# DSO_Counters.net
KiCad netlist of a schematic drawn in Altium Designer
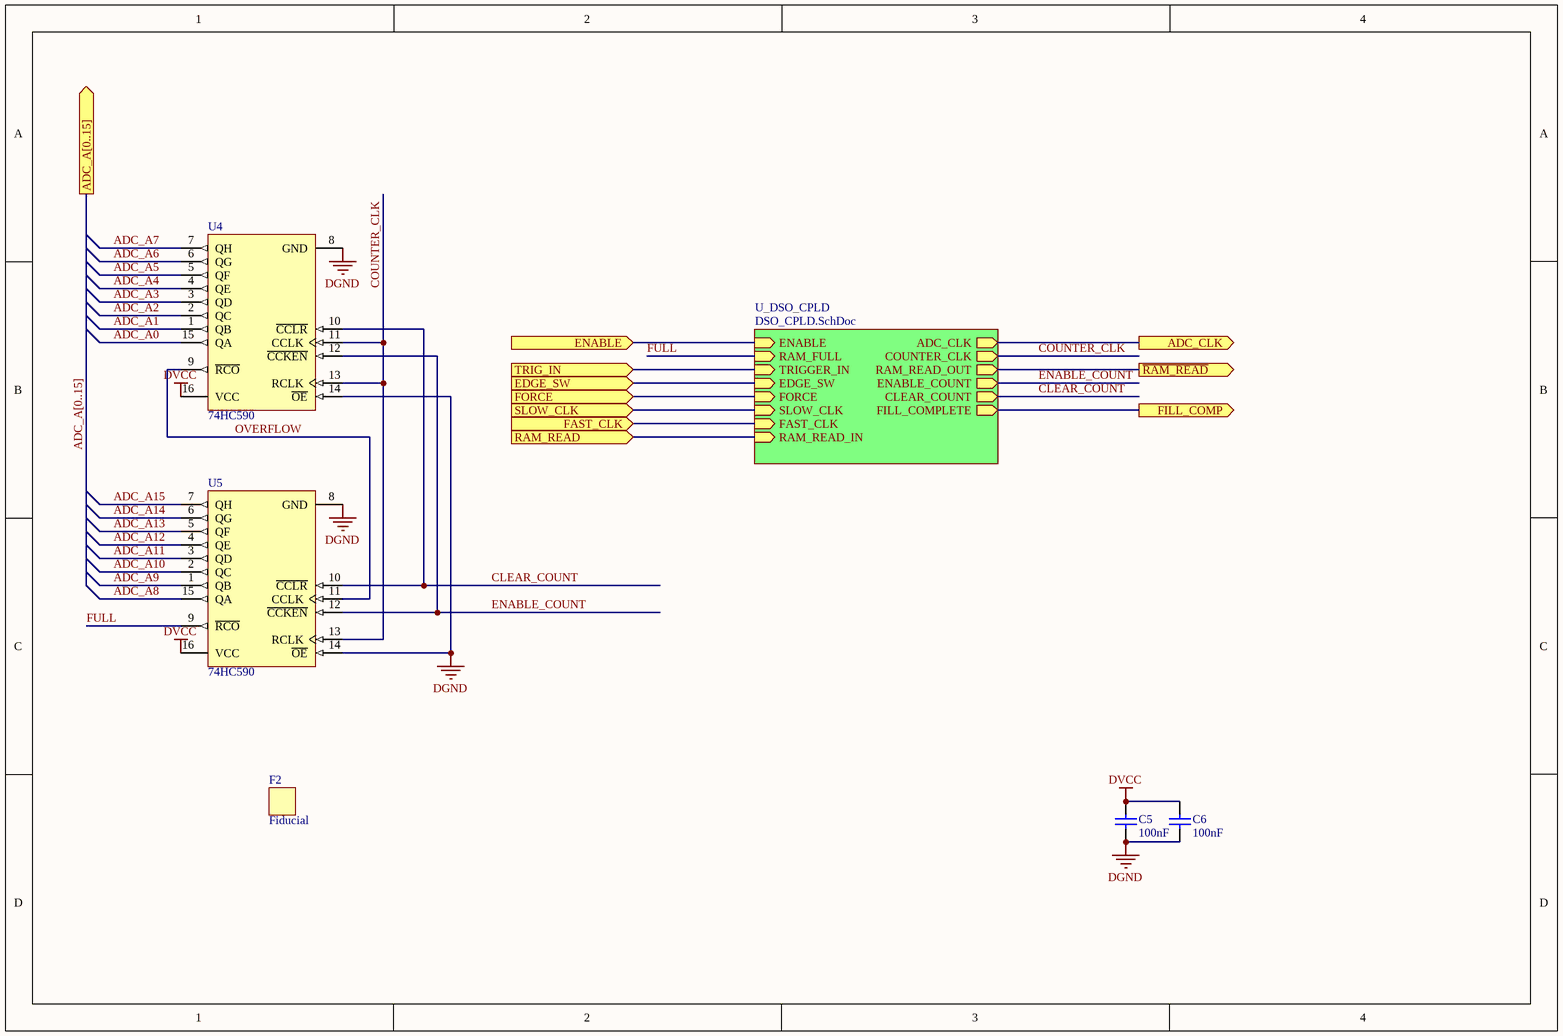
[diagram p0: DSO_Counters.SchDoc]

(export (version "E")
  (design (tool "Eeschema 10.0.6"))
  (components
    (comp (ref "C5")
      (value "100nF")
      (footprint "0805C")
      (description "Capacitor")
      (fields (field (name "REVIEWED BY") "RM - 2018/08/05"))
      (libsource (lib "DSO") (part "C"))
    )
    (comp (ref "C6")
      (value "100nF")
      (footprint "0805C")
      (description "Capacitor")
      (fields (field (name "REVIEWED BY") "RM - 2018/08/05"))
      (libsource (lib "DSO") (part "C"))
    )
    (comp (ref "F2") (value "Fiducial") (footprint "Fiducial") (libsource (lib "DSO") (part "Fiducial")))
    (comp (ref "U4")
      (value "74HC590")
      (footprint "SOIC-16")
      (description "8-Bit Binary Counter Register")
      (fields (field (name "REVIEWED BY") "RM - 2018/08/05"))
      (libsource (lib "DSO") (part "74HC590"))
    )
    (comp (ref "U5")
      (value "74HC590")
      (footprint "SOIC-16")
      (description "8-Bit Binary Counter Register")
      (fields (field (name "REVIEWED BY") "RM - 2018/08/05"))
      (libsource (lib "DSO") (part "74HC590"))
    )
  )
  (nets
    (net (code "1") (name "/ADC_A0") (class "Default")
      (node (ref "U4") (pin "15") (pinfunction "QA_15") (pintype "output"))
    )
    (net (code "2") (name "/ADC_A1") (class "Default")
      (node (ref "U4") (pin "1") (pinfunction "QB_1") (pintype "output"))
    )
    (net (code "3") (name "/ADC_A2") (class "Default")
      (node (ref "U4") (pin "2") (pinfunction "QC_2") (pintype "output"))
    )
    (net (code "4") (name "/ADC_A3") (class "Default")
      (node (ref "U4") (pin "3") (pinfunction "QD_3") (pintype "output"))
    )
    (net (code "5") (name "/ADC_A4") (class "Default")
      (node (ref "U4") (pin "4") (pinfunction "QE_4") (pintype "output"))
    )
    (net (code "6") (name "/ADC_A5") (class "Default")
      (node (ref "U4") (pin "5") (pinfunction "QF_5") (pintype "output"))
    )
    (net (code "7") (name "/ADC_A6") (class "Default")
      (node (ref "U4") (pin "6") (pinfunction "QG_6") (pintype "output"))
    )
    (net (code "8") (name "/ADC_A7") (class "Default")
      (node (ref "U4") (pin "7") (pinfunction "QH_7") (pintype "output"))
    )
    (net (code "9") (name "/ADC_A8") (class "Default")
      (node (ref "U5") (pin "15") (pinfunction "QA_15") (pintype "output"))
    )
    (net (code "10") (name "/ADC_A9") (class "Default")
      (node (ref "U5") (pin "1") (pinfunction "QB_1") (pintype "output"))
    )
    (net (code "11") (name "/ADC_A10") (class "Default")
      (node (ref "U5") (pin "2") (pinfunction "QC_2") (pintype "output"))
    )
    (net (code "12") (name "/ADC_A11") (class "Default")
      (node (ref "U5") (pin "3") (pinfunction "QD_3") (pintype "output"))
    )
    (net (code "13") (name "/ADC_A12") (class "Default")
      (node (ref "U5") (pin "4") (pinfunction "QE_4") (pintype "output"))
    )
    (net (code "14") (name "/ADC_A13") (class "Default")
      (node (ref "U5") (pin "5") (pinfunction "QF_5") (pintype "output"))
    )
    (net (code "15") (name "/ADC_A14") (class "Default")
      (node (ref "U5") (pin "6") (pinfunction "QG_6") (pintype "output"))
    )
    (net (code "16") (name "/ADC_A15") (class "Default")
      (node (ref "U5") (pin "7") (pinfunction "QH_7") (pintype "output"))
    )
    (net (code "19") (name "/CLEAR_COUNT") (class "Default")
      (node (ref "U4") (pin "10") (pinfunction "~{CCLR}_10") (pintype "input"))
      (node (ref "U5") (pin "10") (pinfunction "~{CCLR}_10") (pintype "input"))
    )
    (net (code "20") (name "/COUNTER_CLK") (class "Default")
      (node (ref "U4") (pin "11") (pinfunction "CCLK_11") (pintype "input"))
      (node (ref "U4") (pin "13") (pinfunction "RCLK_13") (pintype "input"))
      (node (ref "U5") (pin "13") (pinfunction "RCLK_13") (pintype "input"))
    )
    (net (code "23") (name "/ENABLE_COUNT") (class "Default")
      (node (ref "U4") (pin "12") (pinfunction "~{CCKEN}_12") (pintype "input"))
      (node (ref "U5") (pin "12") (pinfunction "~{CCKEN}_12") (pintype "input"))
    )
    (net (code "27") (name "/FULL") (class "Default")
      (node (ref "U5") (pin "9") (pinfunction "~{RCO}_9") (pintype "output"))
    )
    (net (code "28") (name "/OVERFLOW") (class "Default")
      (node (ref "U4") (pin "9") (pinfunction "~{RCO}_9") (pintype "output"))
      (node (ref "U5") (pin "11") (pinfunction "CCLK_11") (pintype "input"))
    )
    (net (code "33") (name "DGND") (class "Default")
      (node (ref "C5") (pin "2") (pinfunction "2_2") (pintype "passive"))
      (node (ref "C6") (pin "2") (pinfunction "2_2") (pintype "passive"))
      (node (ref "U4") (pin "14") (pinfunction "~{OE}_14") (pintype "input"))
      (node (ref "U4") (pin "8") (pinfunction "GND_8") (pintype "power_in"))
      (node (ref "U5") (pin "14") (pinfunction "~{OE}_14") (pintype "input"))
      (node (ref "U5") (pin "8") (pinfunction "GND_8") (pintype "power_in"))
    )
    (net (code "34") (name "DVCC") (class "Default")
      (node (ref "C5") (pin "1") (pinfunction "1_1") (pintype "passive"))
      (node (ref "C6") (pin "1") (pinfunction "1_1") (pintype "passive"))
      (node (ref "U4") (pin "16") (pinfunction "VCC_16") (pintype "power_in"))
      (node (ref "U5") (pin "16") (pinfunction "VCC_16") (pintype "power_in"))
    )
  )
)
